# Low_Distortion_Oscillator_LDO.net
KiCad netlist of a schematic drawn in Altium Designer
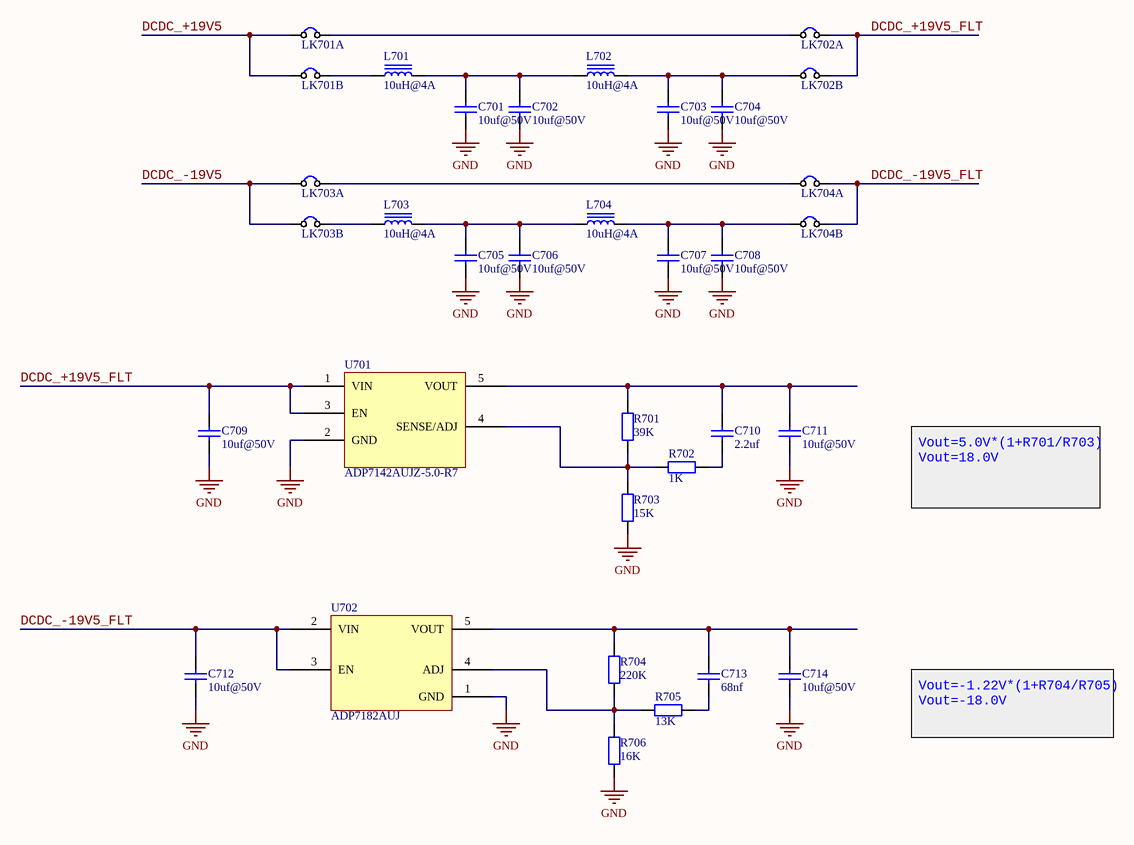
[diagram p0: Low Distortion Oscillator.LDO.SchDoc]

(export (version "E")
  (design (tool "Eeschema 10.0.6"))
  (components
    (comp (ref "C701")
      (value "10uf@50V")
      (footprint "C1206")
      (fields (field (name "Comment") "Cap"))
      (libsource (lib "carrot_lib") (part "Cap"))
    )
    (comp (ref "C702")
      (value "10uf@50V")
      (footprint "C1206")
      (fields (field (name "Comment") "Cap"))
      (libsource (lib "carrot_lib") (part "Cap"))
    )
    (comp (ref "C703")
      (value "10uf@50V")
      (footprint "C1206")
      (fields (field (name "Comment") "Cap"))
      (libsource (lib "carrot_lib") (part "Cap"))
    )
    (comp (ref "C704")
      (value "10uf@50V")
      (footprint "C1206")
      (fields (field (name "Comment") "Cap"))
      (libsource (lib "carrot_lib") (part "Cap"))
    )
    (comp (ref "C705")
      (value "10uf@50V")
      (footprint "C1206")
      (fields (field (name "Comment") "Cap"))
      (libsource (lib "carrot_lib") (part "Cap"))
    )
    (comp (ref "C706")
      (value "10uf@50V")
      (footprint "C1206")
      (fields (field (name "Comment") "Cap"))
      (libsource (lib "carrot_lib") (part "Cap"))
    )
    (comp (ref "C707")
      (value "10uf@50V")
      (footprint "C1206")
      (fields (field (name "Comment") "Cap"))
      (libsource (lib "carrot_lib") (part "Cap"))
    )
    (comp (ref "C708")
      (value "10uf@50V")
      (footprint "C1206")
      (fields (field (name "Comment") "Cap"))
      (libsource (lib "carrot_lib") (part "Cap"))
    )
    (comp (ref "C709")
      (value "10uf@50V")
      (footprint "C1206")
      (fields (field (name "Comment") "Cap"))
      (libsource (lib "carrot_lib") (part "Cap"))
    )
    (comp (ref "C710")
      (value "2.2uf")
      (footprint "C0603")
      (fields (field (name "Comment") "Cap"))
      (libsource (lib "carrot_lib") (part "Cap"))
    )
    (comp (ref "C711")
      (value "10uf@50V")
      (footprint "C1206")
      (fields (field (name "Comment") "Cap"))
      (libsource (lib "carrot_lib") (part "Cap"))
    )
    (comp (ref "C712")
      (value "10uf@50V")
      (footprint "C0805")
      (fields (field (name "Comment") "Cap"))
      (libsource (lib "carrot_lib") (part "Cap"))
    )
    (comp (ref "C713")
      (value "68nf")
      (footprint "C0603")
      (fields (field (name "Comment") "Cap"))
      (libsource (lib "carrot_lib") (part "Cap"))
    )
    (comp (ref "C714")
      (value "10uf@50V")
      (footprint "C1206")
      (fields (field (name "Comment") "Cap"))
      (libsource (lib "carrot_lib") (part "Cap"))
    )
    (comp (ref "L701")
      (value "10uH@4A")
      (footprint "L06063")
      (description "Magnetic-Core Inductor")
      (fields (field (name "Comment") "Inductor Iron"))
      (libsource (lib "carrot_lib") (part "Inductor Iron"))
    )
    (comp (ref "L702")
      (value "10uH@4A")
      (footprint "L06063")
      (description "Magnetic-Core Inductor")
      (fields (field (name "Comment") "Inductor Iron"))
      (libsource (lib "carrot_lib") (part "Inductor Iron"))
    )
    (comp (ref "L703")
      (value "10uH@4A")
      (footprint "L06063")
      (description "Magnetic-Core Inductor")
      (fields (field (name "Comment") "Inductor Iron"))
      (libsource (lib "carrot_lib") (part "Inductor Iron"))
    )
    (comp (ref "L704")
      (value "10uH@4A")
      (footprint "L06063")
      (description "Magnetic-Core Inductor")
      (fields (field (name "Comment") "Inductor Iron"))
      (libsource (lib "carrot_lib") (part "Inductor Iron"))
    )
    (comp (ref "LK701")
      (value "Link-2X2")
      (footprint "Link-2X2-THD")
      (libsource (lib "carrot_lib") (part "Link-2X2"))
    )
    (comp (ref "LK702")
      (value "Link-2X2")
      (footprint "Link-2X2-THD")
      (libsource (lib "carrot_lib") (part "Link-2X2"))
    )
    (comp (ref "LK703")
      (value "Link-2X2")
      (footprint "Link-2X2-THD")
      (libsource (lib "carrot_lib") (part "Link-2X2"))
    )
    (comp (ref "LK704")
      (value "Link-2X2")
      (footprint "Link-2X2-THD")
      (libsource (lib "carrot_lib") (part "Link-2X2"))
    )
    (comp (ref "R701")
      (value "39K")
      (footprint "R0603")
      (description "电阻")
      (fields (field (name "Comment") "Res"))
      (libsource (lib "") (part "Res_1"))
    )
    (comp (ref "R702")
      (value "1K")
      (footprint "R0603")
      (description "电阻")
      (fields (field (name "Comment") "Res"))
      (libsource (lib "carrot_lib") (part "Res"))
    )
    (comp (ref "R703")
      (value "15K")
      (footprint "R0603")
      (description "电阻")
      (fields (field (name "Comment") "Res"))
      (libsource (lib "") (part "Res_1"))
    )
    (comp (ref "R704")
      (value "220K")
      (footprint "R0603")
      (description "电阻")
      (fields (field (name "Comment") "Res"))
      (libsource (lib "") (part "Res_1"))
    )
    (comp (ref "R705")
      (value "13K")
      (footprint "R0603")
      (description "电阻")
      (fields (field (name "Comment") "Res"))
      (libsource (lib "carrot_lib") (part "Res"))
    )
    (comp (ref "R706")
      (value "16K")
      (footprint "R0603")
      (description "电阻")
      (fields (field (name "Comment") "Res"))
      (libsource (lib "") (part "Res_1"))
    )
    (comp (ref "U701")
      (value "ADP7142AUJZ-5.0-R7")
      (footprint "ADP7142-TSOT5")
      (description "40 V, 200 mA, Low Noise, CMOS LDO Linear Regulator")
      (libsource (lib "carrot_lib") (part "ADP7142AUJ"))
    )
    (comp (ref "U702")
      (value "ADP7182AUJ")
      (footprint "ADP7182-TSOT5")
      (description "–28 V, −200 mA, Low Noise, Linear Regulator")
      (libsource (lib "carrot_lib") (part "ADP7182AUJ"))
    )
  )
  (nets
    (net (code "1") (name "/DCDC_+19V5") (class "Default")
      (node (ref "LK701") (pin "1") (pinfunction "1_1") (pintype "passive"))
      (node (ref "LK701") (pin "3") (pinfunction "3_3") (pintype "passive"))
    )
    (net (code "2") (name "/DCDC_+19V5_FLT") (class "Default")
      (node (ref "C709") (pin "2") (pinfunction "2_2") (pintype "passive"))
      (node (ref "LK702") (pin "2") (pinfunction "2_2") (pintype "passive"))
      (node (ref "LK702") (pin "4") (pinfunction "4_4") (pintype "passive"))
      (node (ref "U701") (pin "1") (pinfunction "VIN_1") (pintype "passive"))
      (node (ref "U701") (pin "3") (pinfunction "EN_3") (pintype "passive"))
    )
    (net (code "3") (name "/DCDC_-19V5") (class "Default")
      (node (ref "LK703") (pin "1") (pinfunction "1_1") (pintype "passive"))
      (node (ref "LK703") (pin "3") (pinfunction "3_3") (pintype "passive"))
    )
    (net (code "4") (name "/DCDC_-19V5_FLT") (class "Default")
      (node (ref "C712") (pin "2") (pinfunction "2_2") (pintype "passive"))
      (node (ref "LK704") (pin "2") (pinfunction "2_2") (pintype "passive"))
      (node (ref "LK704") (pin "4") (pinfunction "4_4") (pintype "passive"))
      (node (ref "U702") (pin "2") (pinfunction "VIN_2") (pintype "passive"))
      (node (ref "U702") (pin "3") (pinfunction "EN_3") (pintype "passive"))
    )
    (net (code "5") (name "GND") (class "Default")
      (node (ref "C701") (pin "1") (pinfunction "1_1") (pintype "passive"))
      (node (ref "C702") (pin "1") (pinfunction "1_1") (pintype "passive"))
      (node (ref "C703") (pin "1") (pinfunction "1_1") (pintype "passive"))
      (node (ref "C704") (pin "1") (pinfunction "1_1") (pintype "passive"))
      (node (ref "C705") (pin "1") (pinfunction "1_1") (pintype "passive"))
      (node (ref "C706") (pin "1") (pinfunction "1_1") (pintype "passive"))
      (node (ref "C707") (pin "1") (pinfunction "1_1") (pintype "passive"))
      (node (ref "C708") (pin "1") (pinfunction "1_1") (pintype "passive"))
      (node (ref "C709") (pin "1") (pinfunction "1_1") (pintype "passive"))
      (node (ref "C711") (pin "1") (pinfunction "1_1") (pintype "passive"))
      (node (ref "C712") (pin "1") (pinfunction "1_1") (pintype "passive"))
      (node (ref "C714") (pin "1") (pinfunction "1_1") (pintype "passive"))
      (node (ref "R703") (pin "1") (pinfunction "1_1") (pintype "passive"))
      (node (ref "R706") (pin "1") (pinfunction "1_1") (pintype "passive"))
      (node (ref "U701") (pin "2") (pinfunction "GND_2") (pintype "passive"))
      (node (ref "U702") (pin "1") (pinfunction "GND_1") (pintype "passive"))
    )
    (net (code "6") (name "Net-(C701-Pad2)") (class "Default")
      (node (ref "C701") (pin "2") (pinfunction "2_2") (pintype "passive"))
      (node (ref "C702") (pin "2") (pinfunction "2_2") (pintype "passive"))
      (node (ref "L701") (pin "2") (pinfunction "2_2") (pintype "passive"))
      (node (ref "L702") (pin "1") (pinfunction "1_1") (pintype "passive"))
    )
    (net (code "7") (name "Net-(C703-Pad2)") (class "Default")
      (node (ref "C703") (pin "2") (pinfunction "2_2") (pintype "passive"))
      (node (ref "C704") (pin "2") (pinfunction "2_2") (pintype "passive"))
      (node (ref "L702") (pin "2") (pinfunction "2_2") (pintype "passive"))
      (node (ref "LK702") (pin "3") (pinfunction "3_3") (pintype "passive"))
    )
    (net (code "8") (name "Net-(C705-Pad2)") (class "Default")
      (node (ref "C705") (pin "2") (pinfunction "2_2") (pintype "passive"))
      (node (ref "C706") (pin "2") (pinfunction "2_2") (pintype "passive"))
      (node (ref "L703") (pin "2") (pinfunction "2_2") (pintype "passive"))
      (node (ref "L704") (pin "1") (pinfunction "1_1") (pintype "passive"))
    )
    (net (code "9") (name "Net-(C707-Pad2)") (class "Default")
      (node (ref "C707") (pin "2") (pinfunction "2_2") (pintype "passive"))
      (node (ref "C708") (pin "2") (pinfunction "2_2") (pintype "passive"))
      (node (ref "L704") (pin "2") (pinfunction "2_2") (pintype "passive"))
      (node (ref "LK704") (pin "3") (pinfunction "3_3") (pintype "passive"))
    )
    (net (code "10") (name "Net-(C710-Pad1)") (class "Default")
      (node (ref "C710") (pin "1") (pinfunction "1_1") (pintype "passive"))
      (node (ref "R702") (pin "1") (pinfunction "1_1") (pintype "passive"))
    )
    (net (code "11") (name "Net-(C713-Pad1)") (class "Default")
      (node (ref "C713") (pin "1") (pinfunction "1_1") (pintype "passive"))
      (node (ref "R705") (pin "1") (pinfunction "1_1") (pintype "passive"))
    )
    (net (code "12") (name "Net-(L701-Pad1)") (class "Default")
      (node (ref "L701") (pin "1") (pinfunction "1_1") (pintype "passive"))
      (node (ref "LK701") (pin "4") (pinfunction "4_4") (pintype "passive"))
    )
    (net (code "13") (name "Net-(L703-Pad1)") (class "Default")
      (node (ref "L703") (pin "1") (pinfunction "1_1") (pintype "passive"))
      (node (ref "LK703") (pin "4") (pinfunction "4_4") (pintype "passive"))
    )
    (net (code "14") (name "Net-(LK701-Pad2)") (class "Default")
      (node (ref "LK701") (pin "2") (pinfunction "2_2") (pintype "passive"))
      (node (ref "LK702") (pin "1") (pinfunction "1_1") (pintype "passive"))
    )
    (net (code "15") (name "Net-(LK703-Pad2)") (class "Default")
      (node (ref "LK703") (pin "2") (pinfunction "2_2") (pintype "passive"))
      (node (ref "LK704") (pin "1") (pinfunction "1_1") (pintype "passive"))
    )
    (net (code "16") (name "Net-(U701-SENSE{slash}ADJ)") (class "Default")
      (node (ref "R701") (pin "1") (pinfunction "1_1") (pintype "passive"))
      (node (ref "R702") (pin "2") (pinfunction "2_2") (pintype "passive"))
      (node (ref "R703") (pin "2") (pinfunction "2_2") (pintype "passive"))
      (node (ref "U701") (pin "4") (pinfunction "SENSE/ADJ_4") (pintype "passive"))
    )
    (net (code "17") (name "Net-(U701-VOUT)") (class "Default")
      (node (ref "C710") (pin "2") (pinfunction "2_2") (pintype "passive"))
      (node (ref "C711") (pin "2") (pinfunction "2_2") (pintype "passive"))
      (node (ref "R701") (pin "2") (pinfunction "2_2") (pintype "passive"))
      (node (ref "U701") (pin "5") (pinfunction "VOUT_5") (pintype "passive"))
    )
    (net (code "18") (name "Net-(U702-ADJ)") (class "Default")
      (node (ref "R704") (pin "1") (pinfunction "1_1") (pintype "passive"))
      (node (ref "R705") (pin "2") (pinfunction "2_2") (pintype "passive"))
      (node (ref "R706") (pin "2") (pinfunction "2_2") (pintype "passive"))
      (node (ref "U702") (pin "4") (pinfunction "ADJ_4") (pintype "passive"))
    )
    (net (code "19") (name "Net-(U702-VOUT)") (class "Default")
      (node (ref "C713") (pin "2") (pinfunction "2_2") (pintype "passive"))
      (node (ref "C714") (pin "2") (pinfunction "2_2") (pintype "passive"))
      (node (ref "R704") (pin "2") (pinfunction "2_2") (pintype "passive"))
      (node (ref "U702") (pin "5") (pinfunction "VOUT_5") (pintype "passive"))
    )
  )
)
